# MaWei.net
KiCad netlist of a schematic drawn in Altium Designer
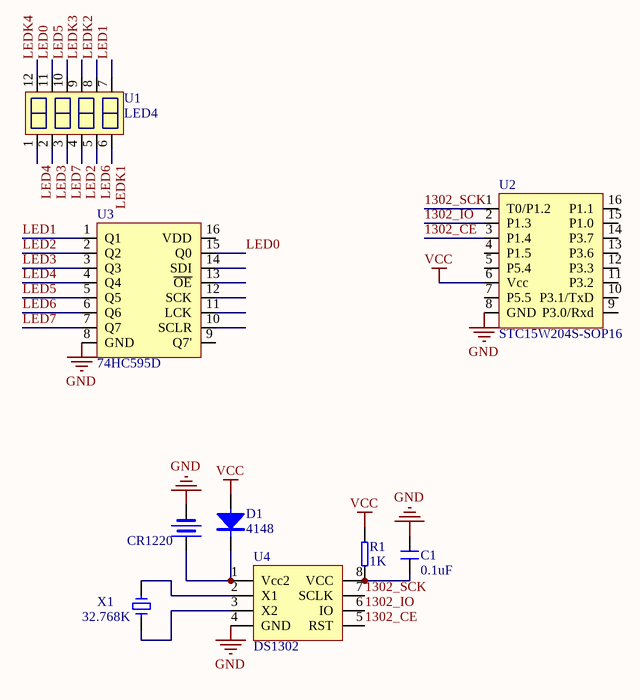
[diagram p0: MaWei.SchDoc]

(export (version "E")
  (design (tool "Eeschema 10.0.6"))
  (components
    (comp (ref "BT1") (value "CR1220") (footprint "CR1220") (libsource (lib "MaWei") (part "BATTERY")))
    (comp (ref "C1") (value "0.1uF") (footprint "RES") (libsource (lib "MaWei") (part "CAP2")))
    (comp (ref "D1") (value "4148") (footprint "LED0805") (libsource (lib "MaWei") (part "Diode")))
    (comp (ref "R1") (value "1K") (footprint "RES0603") (libsource (lib "MaWei") (part "RES")))
    (comp (ref "U1") (value "LED4") (libsource (lib "MaWei") (part "LED4")))
    (comp (ref "U2")
      (value "STC15W204S-SOP16")
      (footprint "SOP16")
      (libsource (lib "MaWei") (part "STC15W204S-SOP16"))
    )
    (comp (ref "U3") (value "74HC595D") (footprint "SOP16") (libsource (lib "MaWei") (part "74HC595D")))
    (comp (ref "U4") (value "DS1302") (footprint "SOP8") (libsource (lib "MaWei") (part "DS1302")))
    (comp (ref "X1") (value "32.768K") (footprint "FC-135") (libsource (lib "MaWei") (part "XTAL")))
  )
  (nets
    (net (code "1") (name "/1302_CE") (class "Default")
      (node (ref "U2") (pin "3") (pinfunction "P1.4_3") (pintype "passive"))
      (node (ref "U4") (pin "5") (pinfunction "RST_5") (pintype "passive"))
    )
    (net (code "2") (name "/1302_IO") (class "Default")
      (node (ref "U2") (pin "2") (pinfunction "P1.3_2") (pintype "passive"))
      (node (ref "U4") (pin "6") (pinfunction "IO_6") (pintype "passive"))
    )
    (net (code "3") (name "/1302_SCK") (class "Default")
      (node (ref "U2") (pin "1") (pinfunction "T0/P1.2_1") (pintype "passive"))
      (node (ref "U4") (pin "7") (pinfunction "SCLK_7") (pintype "passive"))
    )
    (net (code "4") (name "/LED0") (class "Default")
      (node (ref "U1") (pin "11") (pintype "passive"))
      (node (ref "U3") (pin "15") (pinfunction "Q0_15") (pintype "passive"))
    )
    (net (code "5") (name "/LED1") (class "Default")
      (node (ref "U1") (pin "7") (pintype "passive"))
      (node (ref "U3") (pin "1") (pinfunction "Q1_1") (pintype "passive"))
    )
    (net (code "6") (name "/LED2") (class "Default")
      (node (ref "U1") (pin "4") (pintype "passive"))
      (node (ref "U3") (pin "2") (pinfunction "Q2_2") (pintype "passive"))
    )
    (net (code "7") (name "/LED3") (class "Default")
      (node (ref "U1") (pin "2") (pintype "passive"))
      (node (ref "U3") (pin "3") (pinfunction "Q3_3") (pintype "passive"))
    )
    (net (code "8") (name "/LED4") (class "Default")
      (node (ref "U1") (pin "1") (pintype "passive"))
      (node (ref "U3") (pin "4") (pinfunction "Q4_4") (pintype "passive"))
    )
    (net (code "9") (name "/LED5") (class "Default")
      (node (ref "U1") (pin "10") (pintype "passive"))
      (node (ref "U3") (pin "5") (pinfunction "Q5_5") (pintype "passive"))
    )
    (net (code "10") (name "/LED6") (class "Default")
      (node (ref "U1") (pin "5") (pintype "passive"))
      (node (ref "U3") (pin "6") (pinfunction "Q6_6") (pintype "passive"))
    )
    (net (code "11") (name "/LED7") (class "Default")
      (node (ref "U1") (pin "3") (pintype "passive"))
      (node (ref "U3") (pin "7") (pinfunction "Q7_7") (pintype "passive"))
    )
    (net (code "12") (name "/LEDK1") (class "Default") (node (ref "U1") (pin "6") (pintype "passive")))
    (net (code "13") (name "/LEDK2") (class "Default") (node (ref "U1") (pin "8") (pintype "passive")))
    (net (code "14") (name "/LEDK3") (class "Default") (node (ref "U1") (pin "9") (pintype "passive")))
    (net (code "15") (name "/LEDK4") (class "Default") (node (ref "U1") (pin "12") (pintype "passive")))
    (net (code "16") (name "GND") (class "Default")
      (node (ref "BT1") (pin "2") (pinfunction "-_2") (pintype "passive"))
      (node (ref "C1") (pin "2") (pintype "passive"))
      (node (ref "U2") (pin "8") (pinfunction "GND_8") (pintype "passive"))
      (node (ref "U3") (pin "8") (pinfunction "GND_8") (pintype "passive"))
      (node (ref "U4") (pin "4") (pinfunction "GND_4") (pintype "passive"))
    )
    (net (code "17") (name "Net-(BT1-+)") (class "Default")
      (node (ref "BT1") (pin "1") (pinfunction "+_1") (pintype "passive"))
      (node (ref "D1") (pin "2") (pinfunction "K_2") (pintype "passive"))
      (node (ref "U4") (pin "1") (pinfunction "Vcc2_1") (pintype "passive"))
    )
    (net (code "18") (name "Net-(U4-VCC)") (class "Default")
      (node (ref "C1") (pin "1") (pintype "passive"))
      (node (ref "R1") (pin "1") (pinfunction "1_1") (pintype "passive"))
      (node (ref "U4") (pin "8") (pinfunction "VCC_8") (pintype "passive"))
    )
    (net (code "19") (name "Net-(U4-X1)") (class "Default")
      (node (ref "U4") (pin "2") (pinfunction "X1_2") (pintype "passive"))
      (node (ref "X1") (pin "2") (pinfunction "2_2") (pintype "passive"))
    )
    (net (code "20") (name "Net-(U4-X2)") (class "Default")
      (node (ref "U4") (pin "3") (pinfunction "X2_3") (pintype "passive"))
      (node (ref "X1") (pin "1") (pinfunction "1_1") (pintype "passive"))
    )
    (net (code "21") (name "VCC") (class "Default")
      (node (ref "D1") (pin "1") (pinfunction "A_1") (pintype "passive"))
      (node (ref "R1") (pin "2") (pinfunction "2_2") (pintype "passive"))
      (node (ref "U2") (pin "6") (pinfunction "Vcc_6") (pintype "passive"))
    )
    (net (code "22") (name "unconnected-(U2-P1.0-Pad15)") (class "Default")
      (node (ref "U2") (pin "15") (pinfunction "P1.0_15") (pintype "passive"))
    )
    (net (code "23") (name "unconnected-(U2-P1.1-Pad16)") (class "Default")
      (node (ref "U2") (pin "16") (pinfunction "P1.1_16") (pintype "passive"))
    )
    (net (code "24") (name "unconnected-(U2-P1.5-Pad4)") (class "Default")
      (node (ref "U2") (pin "4") (pinfunction "P1.5_4") (pintype "passive"))
    )
    (net (code "25") (name "unconnected-(U2-P3.0{slash}Rxd-Pad9)") (class "Default")
      (node (ref "U2") (pin "9") (pinfunction "P3.0/Rxd_9") (pintype "passive"))
    )
    (net (code "26") (name "unconnected-(U2-P3.1{slash}TxD-Pad10)") (class "Default")
      (node (ref "U2") (pin "10") (pinfunction "P3.1/TxD_10") (pintype "passive"))
    )
    (net (code "27") (name "unconnected-(U2-P3.2-Pad11)") (class "Default")
      (node (ref "U2") (pin "11") (pinfunction "P3.2_11") (pintype "passive"))
    )
    (net (code "28") (name "unconnected-(U2-P3.3-Pad12)") (class "Default")
      (node (ref "U2") (pin "12") (pinfunction "P3.3_12") (pintype "passive"))
    )
    (net (code "29") (name "unconnected-(U2-P3.6-Pad13)") (class "Default")
      (node (ref "U2") (pin "13") (pinfunction "P3.6_13") (pintype "passive"))
    )
    (net (code "30") (name "unconnected-(U2-P3.7-Pad14)") (class "Default")
      (node (ref "U2") (pin "14") (pinfunction "P3.7_14") (pintype "passive"))
    )
    (net (code "31") (name "unconnected-(U2-P5.4-Pad5)") (class "Default")
      (node (ref "U2") (pin "5") (pinfunction "P5.4_5") (pintype "passive"))
    )
    (net (code "32") (name "unconnected-(U2-P5.5-Pad7)") (class "Default")
      (node (ref "U2") (pin "7") (pinfunction "P5.5_7") (pintype "passive"))
    )
    (net (code "33") (name "unconnected-(U3-LCK-Pad11)") (class "Default")
      (node (ref "U3") (pin "11") (pinfunction "LCK_11") (pintype "passive"))
    )
    (net (code "34") (name "unconnected-(U3-Q7'-Pad9)") (class "Default")
      (node (ref "U3") (pin "9") (pinfunction "Q7'_9") (pintype "passive"))
    )
    (net (code "35") (name "unconnected-(U3-SCK-Pad12)") (class "Default")
      (node (ref "U3") (pin "12") (pinfunction "SCK_12") (pintype "passive"))
    )
    (net (code "36") (name "unconnected-(U3-SCLR-Pad10)") (class "Default")
      (node (ref "U3") (pin "10") (pinfunction "SCLR_10") (pintype "passive"))
    )
    (net (code "37") (name "unconnected-(U3-SDI-Pad14)") (class "Default")
      (node (ref "U3") (pin "14") (pinfunction "SDI_14") (pintype "passive"))
    )
    (net (code "38") (name "unconnected-(U3-VDD-Pad16)") (class "Default")
      (node (ref "U3") (pin "16") (pinfunction "VDD_16") (pintype "passive"))
    )
    (net (code "39") (name "unconnected-(U3-~{OE}-Pad13)") (class "Default")
      (node (ref "U3") (pin "13") (pinfunction "~{OE}_13") (pintype "passive"))
    )
  )
)
